# led-regulator.net
KiCad netlist of a schematic drawn in EAGLE
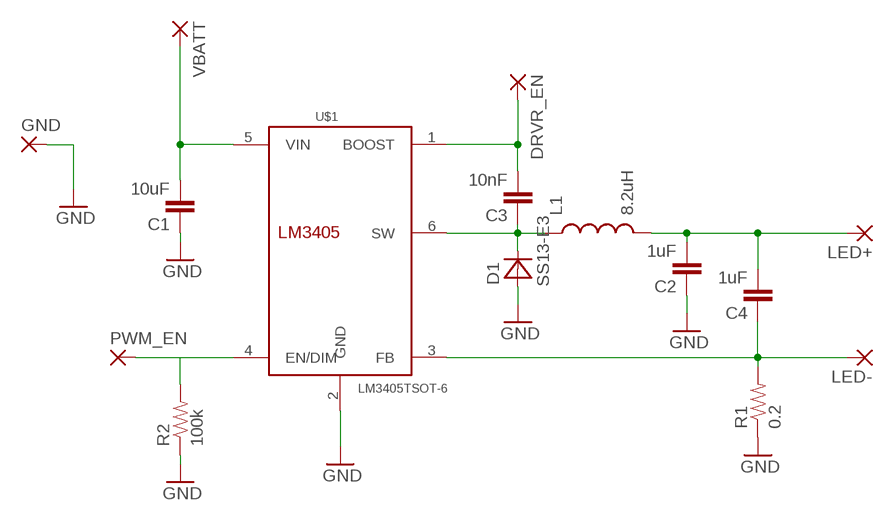
[diagram p0: schematic, sheet 1]

(export (version "E")
  (design (tool "Eeschema 10.0.6"))
  (components
    (comp (ref "C1")
      (value "10uF")
      (footprint "eagle-import:1206")
      (libsource (lib "eagle-import") (part "CAP1206"))
    )
    (comp (ref "C2")
      (value "1uF")
      (footprint "eagle-import:1206")
      (libsource (lib "eagle-import") (part "CAP1206"))
    )
    (comp (ref "C3")
      (value "10nF")
      (footprint "eagle-import:0805")
      (libsource (lib "eagle-import") (part "CAP0805"))
    )
    (comp (ref "C4")
      (value "1uF")
      (footprint "eagle-import:0805")
      (libsource (lib "eagle-import") (part "CAP0805"))
    )
    (comp (ref "D1")
      (value "SS13-E3")
      (footprint "eagle-import:SMA")
      (libsource (lib "eagle-import") (part "MBRA340T3"))
    )
    (comp (ref "DRVR_EN")
      (value "WIREPAD2,15/1,0")
      (footprint "eagle-import:2,15_1,0")
      (libsource (lib "eagle-import") (part "WIREPAD2,15/1,0"))
    )
    (comp (ref "GND")
      (value "WIREPAD2,15/1,0")
      (footprint "eagle-import:2,15_1,0")
      (libsource (lib "eagle-import") (part "WIREPAD2,15/1,0"))
    )
    (comp (ref "L1")
      (value "8.2uH")
      (footprint "eagle-import:1210")
      (libsource (lib "eagle-import") (part "INDUCTOR1210"))
    )
    (comp (ref "LED+")
      (value "WIREPAD2,15/1,0")
      (footprint "eagle-import:2,15_1,0")
      (libsource (lib "eagle-import") (part "WIREPAD2,15/1,0"))
    )
    (comp (ref "LED-")
      (value "WIREPAD2,15/1,0")
      (footprint "eagle-import:2,15_1,0")
      (libsource (lib "eagle-import") (part "WIREPAD2,15/1,0"))
    )
    (comp (ref "PWM_EN")
      (value "WIREPAD2,15/1,0")
      (footprint "eagle-import:2,15_1,0")
      (libsource (lib "eagle-import") (part "WIREPAD2,15/1,0"))
    )
    (comp (ref "R1")
      (value "0.2")
      (footprint "eagle-import:R2010")
      (libsource (lib "eagle-import") (part "RESISTOR2010"))
    )
    (comp (ref "R2")
      (value "100k")
      (footprint "eagle-import:1206")
      (libsource (lib "eagle-import") (part "RESISTOR1206"))
    )
    (comp (ref "U$1")
      (value "LM3405TSOT-6")
      (footprint "eagle-import:TSOT-6")
      (libsource (lib "eagle-import") (part "LM3405TSOT-6"))
    )
    (comp (ref "VBATT")
      (value "WIREPAD2,15/1,0")
      (footprint "eagle-import:2,15_1,0")
      (libsource (lib "eagle-import") (part "WIREPAD2,15/1,0"))
    )
  )
  (nets
    (net (code "1") (name "GND") (class "Default")
      (node (ref "C1") (pin "1") (pinfunction "1_1") (pintype "passive"))
      (node (ref "C2") (pin "1") (pinfunction "1_1") (pintype "passive"))
      (node (ref "D1") (pin "A") (pinfunction "A_A") (pintype "passive"))
      (node (ref "GND") (pin "1") (pinfunction "P_1") (pintype "passive"))
      (node (ref "R1") (pin "1") (pinfunction "1_1") (pintype "passive"))
      (node (ref "R2") (pin "1") (pinfunction "1_1") (pintype "passive"))
      (node (ref "U$1") (pin "2") (pinfunction "GND_2") (pintype "bidirectional"))
    )
    (net (code "2") (name "Net-(DRVR_EN-P)") (class "Default")
      (node (ref "C3") (pin "2") (pinfunction "2_2") (pintype "passive"))
      (node (ref "DRVR_EN") (pin "1") (pinfunction "P_1") (pintype "passive"))
      (node (ref "U$1") (pin "1") (pinfunction "BOOST_1") (pintype "bidirectional"))
    )
    (net (code "3") (name "Net-(LED+-P)") (class "Default")
      (node (ref "C2") (pin "2") (pinfunction "2_2") (pintype "passive"))
      (node (ref "C4") (pin "2") (pinfunction "2_2") (pintype "passive"))
      (node (ref "L1") (pin "2") (pinfunction "2_2") (pintype "passive"))
      (node (ref "LED+") (pin "1") (pinfunction "P_1") (pintype "passive"))
    )
    (net (code "4") (name "Net-(LED--P)") (class "Default")
      (node (ref "C4") (pin "1") (pinfunction "1_1") (pintype "passive"))
      (node (ref "LED-") (pin "1") (pinfunction "P_1") (pintype "passive"))
      (node (ref "R1") (pin "2") (pinfunction "2_2") (pintype "passive"))
      (node (ref "U$1") (pin "3") (pinfunction "FB_3") (pintype "bidirectional"))
    )
    (net (code "5") (name "Net-(PWM_EN-P)") (class "Default")
      (node (ref "PWM_EN") (pin "1") (pinfunction "P_1") (pintype "passive"))
      (node (ref "R2") (pin "2") (pinfunction "2_2") (pintype "passive"))
      (node (ref "U$1") (pin "4") (pinfunction "EN/DIM_4") (pintype "bidirectional"))
    )
    (net (code "6") (name "Net-(U$1-SW)") (class "Default")
      (node (ref "C3") (pin "1") (pinfunction "1_1") (pintype "passive"))
      (node (ref "D1") (pin "C") (pinfunction "C_C") (pintype "passive"))
      (node (ref "L1") (pin "1") (pinfunction "1_1") (pintype "passive"))
      (node (ref "U$1") (pin "6") (pinfunction "SW_6") (pintype "bidirectional"))
    )
    (net (code "7") (name "Net-(U$1-VIN)") (class "Default")
      (node (ref "C1") (pin "2") (pinfunction "2_2") (pintype "passive"))
      (node (ref "U$1") (pin "5") (pinfunction "VIN_5") (pintype "bidirectional"))
      (node (ref "VBATT") (pin "1") (pinfunction "P_1") (pintype "passive"))
    )
  )
)
